# abletondevicecontroller.net
KiCad netlist of a schematic drawn in EAGLE
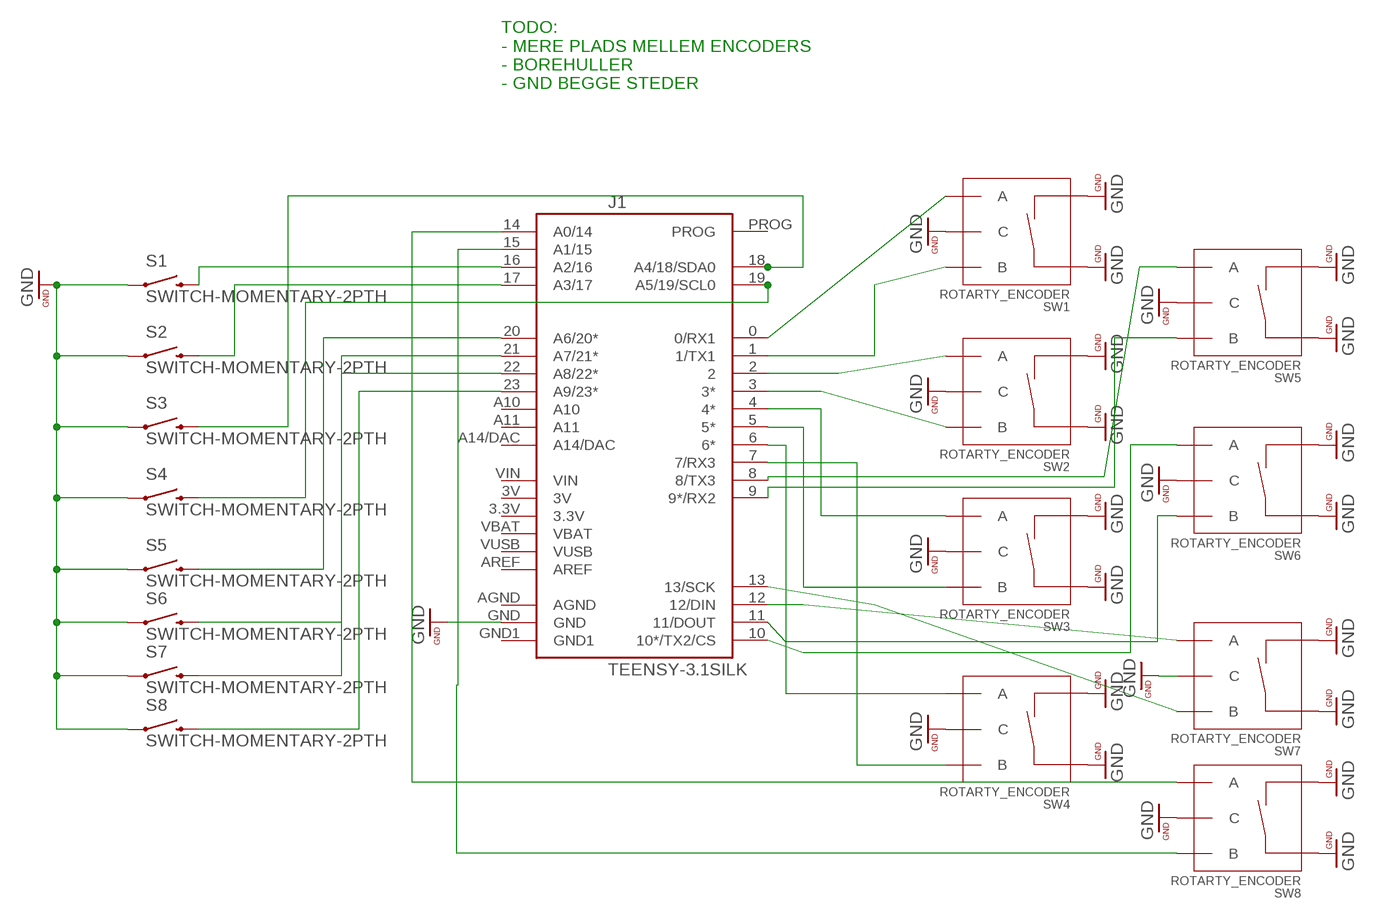
[diagram p0: schematic, sheet 1]

(export (version "E")
  (design (tool "Eeschema 10.0.6"))
  (components
    (comp (ref "J1")
      (value "TEENSY-3.1SILK")
      (footprint "eagle-import:TEENSY-3.1")
      (libsource (lib "eagle-import") (part "TEENSY-3.1SILK"))
    )
    (comp (ref "S1")
      (value "SWITCH-MOMENTARY-2PTH")
      (footprint "eagle-import:TACTILE-PTH")
      (libsource (lib "eagle-import") (part "SWITCH-MOMENTARY-2PTH"))
    )
    (comp (ref "S2")
      (value "SWITCH-MOMENTARY-2PTH")
      (footprint "eagle-import:TACTILE-PTH")
      (libsource (lib "eagle-import") (part "SWITCH-MOMENTARY-2PTH"))
    )
    (comp (ref "S3")
      (value "SWITCH-MOMENTARY-2PTH")
      (footprint "eagle-import:TACTILE-PTH")
      (libsource (lib "eagle-import") (part "SWITCH-MOMENTARY-2PTH"))
    )
    (comp (ref "S4")
      (value "SWITCH-MOMENTARY-2PTH")
      (footprint "eagle-import:TACTILE-PTH")
      (libsource (lib "eagle-import") (part "SWITCH-MOMENTARY-2PTH"))
    )
    (comp (ref "S5")
      (value "SWITCH-MOMENTARY-2PTH")
      (footprint "eagle-import:TACTILE-PTH")
      (libsource (lib "eagle-import") (part "SWITCH-MOMENTARY-2PTH"))
    )
    (comp (ref "S6")
      (value "SWITCH-MOMENTARY-2PTH")
      (footprint "eagle-import:TACTILE-PTH")
      (libsource (lib "eagle-import") (part "SWITCH-MOMENTARY-2PTH"))
    )
    (comp (ref "S7")
      (value "SWITCH-MOMENTARY-2PTH")
      (footprint "eagle-import:TACTILE-PTH")
      (libsource (lib "eagle-import") (part "SWITCH-MOMENTARY-2PTH"))
    )
    (comp (ref "S8")
      (value "SWITCH-MOMENTARY-2PTH")
      (footprint "eagle-import:TACTILE-PTH")
      (libsource (lib "eagle-import") (part "SWITCH-MOMENTARY-2PTH"))
    )
    (comp (ref "SW1")
      (value "ROTARTY_ENCODER")
      (footprint "eagle-import:ROTARY_ENC_PLAIN")
      (libsource (lib "eagle-import") (part "ROTARTY_ENCODER"))
    )
    (comp (ref "SW2")
      (value "ROTARTY_ENCODER")
      (footprint "eagle-import:ROTARY_ENC_PLAIN")
      (libsource (lib "eagle-import") (part "ROTARTY_ENCODER"))
    )
    (comp (ref "SW3")
      (value "ROTARTY_ENCODER")
      (footprint "eagle-import:ROTARY_ENC_PLAIN")
      (libsource (lib "eagle-import") (part "ROTARTY_ENCODER"))
    )
    (comp (ref "SW4")
      (value "ROTARTY_ENCODER")
      (footprint "eagle-import:ROTARY_ENC_PLAIN")
      (libsource (lib "eagle-import") (part "ROTARTY_ENCODER"))
    )
    (comp (ref "SW5")
      (value "ROTARTY_ENCODER")
      (footprint "eagle-import:ROTARY_ENC_PLAIN")
      (libsource (lib "eagle-import") (part "ROTARTY_ENCODER"))
    )
    (comp (ref "SW6")
      (value "ROTARTY_ENCODER")
      (footprint "eagle-import:ROTARY_ENC_PLAIN")
      (libsource (lib "eagle-import") (part "ROTARTY_ENCODER"))
    )
    (comp (ref "SW7")
      (value "ROTARTY_ENCODER")
      (footprint "eagle-import:ROTARY_ENC_PLAIN")
      (libsource (lib "eagle-import") (part "ROTARTY_ENCODER"))
    )
    (comp (ref "SW8")
      (value "ROTARTY_ENCODER")
      (footprint "eagle-import:ROTARY_ENC_PLAIN")
      (libsource (lib "eagle-import") (part "ROTARTY_ENCODER"))
    )
  )
  (nets
    (net (code "1") (name "GND") (class "Default")
      (node (ref "J1") (pin "GND") (pinfunction "GND_GND") (pintype "bidirectional"))
      (node (ref "S1") (pin "1") (pinfunction "1_1") (pintype "passive"))
      (node (ref "S2") (pin "1") (pinfunction "1_1") (pintype "passive"))
      (node (ref "S3") (pin "1") (pinfunction "1_1") (pintype "passive"))
      (node (ref "S4") (pin "1") (pinfunction "1_1") (pintype "passive"))
      (node (ref "S5") (pin "1") (pinfunction "1_1") (pintype "passive"))
      (node (ref "S6") (pin "1") (pinfunction "1_1") (pintype "passive"))
      (node (ref "S7") (pin "1") (pinfunction "1_1") (pintype "passive"))
      (node (ref "S8") (pin "1") (pinfunction "1_1") (pintype "passive"))
      (node (ref "SW1") (pin "C") (pinfunction "C_C") (pintype "bidirectional"))
      (node (ref "SW1") (pin "SW+") (pinfunction "SW+_SW+") (pintype "bidirectional"))
      (node (ref "SW1") (pin "SW-") (pinfunction "SW-_SW-") (pintype "bidirectional"))
      (node (ref "SW2") (pin "C") (pinfunction "C_C") (pintype "bidirectional"))
      (node (ref "SW2") (pin "SW+") (pinfunction "SW+_SW+") (pintype "bidirectional"))
      (node (ref "SW2") (pin "SW-") (pinfunction "SW-_SW-") (pintype "bidirectional"))
      (node (ref "SW3") (pin "C") (pinfunction "C_C") (pintype "bidirectional"))
      (node (ref "SW3") (pin "SW+") (pinfunction "SW+_SW+") (pintype "bidirectional"))
      (node (ref "SW3") (pin "SW-") (pinfunction "SW-_SW-") (pintype "bidirectional"))
      (node (ref "SW4") (pin "C") (pinfunction "C_C") (pintype "bidirectional"))
      (node (ref "SW4") (pin "SW+") (pinfunction "SW+_SW+") (pintype "bidirectional"))
      (node (ref "SW4") (pin "SW-") (pinfunction "SW-_SW-") (pintype "bidirectional"))
      (node (ref "SW5") (pin "C") (pinfunction "C_C") (pintype "bidirectional"))
      (node (ref "SW5") (pin "SW+") (pinfunction "SW+_SW+") (pintype "bidirectional"))
      (node (ref "SW5") (pin "SW-") (pinfunction "SW-_SW-") (pintype "bidirectional"))
      (node (ref "SW6") (pin "C") (pinfunction "C_C") (pintype "bidirectional"))
      (node (ref "SW6") (pin "SW+") (pinfunction "SW+_SW+") (pintype "bidirectional"))
      (node (ref "SW6") (pin "SW-") (pinfunction "SW-_SW-") (pintype "bidirectional"))
      (node (ref "SW7") (pin "C") (pinfunction "C_C") (pintype "bidirectional"))
      (node (ref "SW7") (pin "SW+") (pinfunction "SW+_SW+") (pintype "bidirectional"))
      (node (ref "SW7") (pin "SW-") (pinfunction "SW-_SW-") (pintype "bidirectional"))
      (node (ref "SW8") (pin "C") (pinfunction "C_C") (pintype "bidirectional"))
      (node (ref "SW8") (pin "SW+") (pinfunction "SW+_SW+") (pintype "bidirectional"))
      (node (ref "SW8") (pin "SW-") (pinfunction "SW-_SW-") (pintype "bidirectional"))
    )
    (net (code "2") (name "Net-(J1-0{slash}RX1)") (class "Default")
      (node (ref "J1") (pin "0") (pinfunction "0/RX1_0") (pintype "bidirectional"))
      (node (ref "SW1") (pin "A") (pinfunction "A_A") (pintype "bidirectional"))
    )
    (net (code "3") (name "Net-(J1-1{slash}TX1)") (class "Default")
      (node (ref "J1") (pin "1") (pinfunction "1/TX1_1") (pintype "bidirectional"))
      (node (ref "SW1") (pin "B") (pinfunction "B_B") (pintype "bidirectional"))
    )
    (net (code "4") (name "Net-(J1-3*)") (class "Default")
      (node (ref "J1") (pin "3") (pinfunction "3*_3") (pintype "bidirectional"))
      (node (ref "SW2") (pin "B") (pinfunction "B_B") (pintype "bidirectional"))
    )
    (net (code "5") (name "Net-(J1-4*)") (class "Default")
      (node (ref "J1") (pin "4") (pinfunction "4*_4") (pintype "bidirectional"))
      (node (ref "SW3") (pin "A") (pinfunction "A_A") (pintype "bidirectional"))
    )
    (net (code "6") (name "Net-(J1-5*)") (class "Default")
      (node (ref "J1") (pin "5") (pinfunction "5*_5") (pintype "bidirectional"))
      (node (ref "SW3") (pin "B") (pinfunction "B_B") (pintype "bidirectional"))
    )
    (net (code "7") (name "Net-(J1-6*)") (class "Default")
      (node (ref "J1") (pin "6") (pinfunction "6*_6") (pintype "bidirectional"))
      (node (ref "SW4") (pin "A") (pinfunction "A_A") (pintype "bidirectional"))
    )
    (net (code "8") (name "Net-(J1-7{slash}RX3)") (class "Default")
      (node (ref "J1") (pin "7") (pinfunction "7/RX3_7") (pintype "bidirectional"))
      (node (ref "SW4") (pin "B") (pinfunction "B_B") (pintype "bidirectional"))
    )
    (net (code "9") (name "Net-(J1-8{slash}TX3)") (class "Default")
      (node (ref "J1") (pin "8") (pinfunction "8/TX3_8") (pintype "bidirectional"))
      (node (ref "SW5") (pin "A") (pinfunction "A_A") (pintype "bidirectional"))
    )
    (net (code "10") (name "Net-(J1-9*{slash}RX2)") (class "Default")
      (node (ref "J1") (pin "9") (pinfunction "9*/RX2_9") (pintype "bidirectional"))
      (node (ref "SW5") (pin "B") (pinfunction "B_B") (pintype "bidirectional"))
    )
    (net (code "11") (name "Net-(J1-10*{slash}TX2{slash}CS)") (class "Default")
      (node (ref "J1") (pin "10") (pinfunction "10*/TX2/CS_10") (pintype "bidirectional"))
      (node (ref "SW6") (pin "A") (pinfunction "A_A") (pintype "bidirectional"))
    )
    (net (code "12") (name "Net-(J1-11{slash}DOUT)") (class "Default")
      (node (ref "J1") (pin "11") (pinfunction "11/DOUT_11") (pintype "bidirectional"))
      (node (ref "SW6") (pin "B") (pinfunction "B_B") (pintype "bidirectional"))
    )
    (net (code "13") (name "Net-(J1-12{slash}DIN)") (class "Default")
      (node (ref "J1") (pin "12") (pinfunction "12/DIN_12") (pintype "bidirectional"))
      (node (ref "SW7") (pin "A") (pinfunction "A_A") (pintype "bidirectional"))
    )
    (net (code "14") (name "Net-(J1-13{slash}SCK)") (class "Default")
      (node (ref "J1") (pin "13") (pinfunction "13/SCK_13") (pintype "bidirectional"))
      (node (ref "SW7") (pin "B") (pinfunction "B_B") (pintype "bidirectional"))
    )
    (net (code "15") (name "Net-(J1-A0{slash}14)") (class "Default")
      (node (ref "J1") (pin "14") (pinfunction "A0/14_14") (pintype "bidirectional"))
      (node (ref "SW8") (pin "A") (pinfunction "A_A") (pintype "bidirectional"))
    )
    (net (code "16") (name "Net-(J1-A1{slash}15)") (class "Default")
      (node (ref "J1") (pin "15") (pinfunction "A1/15_15") (pintype "bidirectional"))
      (node (ref "SW8") (pin "B") (pinfunction "B_B") (pintype "bidirectional"))
    )
    (net (code "17") (name "Net-(J1-A2{slash}16)") (class "Default")
      (node (ref "J1") (pin "16") (pinfunction "A2/16_16") (pintype "bidirectional"))
      (node (ref "S1") (pin "3") (pinfunction "2_3") (pintype "passive"))
    )
    (net (code "18") (name "Net-(J1-A3{slash}17)") (class "Default")
      (node (ref "J1") (pin "17") (pinfunction "A3/17_17") (pintype "bidirectional"))
      (node (ref "S2") (pin "3") (pinfunction "2_3") (pintype "passive"))
    )
    (net (code "19") (name "Net-(J1-A4{slash}18{slash}SDA0)") (class "Default")
      (node (ref "J1") (pin "18") (pinfunction "A4/18/SDA0_18") (pintype "bidirectional"))
      (node (ref "S3") (pin "3") (pinfunction "2_3") (pintype "passive"))
    )
    (net (code "20") (name "Net-(J1-A5{slash}19{slash}SCL0)") (class "Default")
      (node (ref "J1") (pin "19") (pinfunction "A5/19/SCL0_19") (pintype "bidirectional"))
      (node (ref "S4") (pin "3") (pinfunction "2_3") (pintype "passive"))
    )
    (net (code "21") (name "Net-(J1-A6{slash}20*)") (class "Default")
      (node (ref "J1") (pin "20") (pinfunction "A6/20*_20") (pintype "bidirectional"))
      (node (ref "S5") (pin "3") (pinfunction "2_3") (pintype "passive"))
    )
    (net (code "22") (name "Net-(J1-A7{slash}21*)") (class "Default")
      (node (ref "J1") (pin "21") (pinfunction "A7/21*_21") (pintype "bidirectional"))
      (node (ref "S6") (pin "3") (pinfunction "2_3") (pintype "passive"))
    )
    (net (code "23") (name "Net-(J1-A8{slash}22*)") (class "Default")
      (node (ref "J1") (pin "22") (pinfunction "A8/22*_22") (pintype "bidirectional"))
      (node (ref "S7") (pin "3") (pinfunction "2_3") (pintype "passive"))
    )
    (net (code "24") (name "Net-(J1-A9{slash}23*)") (class "Default")
      (node (ref "J1") (pin "23") (pinfunction "A9/23*_23") (pintype "bidirectional"))
      (node (ref "S8") (pin "3") (pinfunction "2_3") (pintype "passive"))
    )
    (net (code "25") (name "Net-(J1-Pad2)") (class "Default")
      (node (ref "J1") (pin "2") (pinfunction "2_2") (pintype "bidirectional"))
      (node (ref "SW2") (pin "A") (pinfunction "A_A") (pintype "bidirectional"))
    )
    (net (code "26") (name "unconnected-(J1-Pad3.3V)") (class "Default")
      (node (ref "J1") (pin "3.3V") (pinfunction "3.3V_3.3V") (pintype "bidirectional"))
    )
    (net (code "27") (name "unconnected-(J1-Pad3V)") (class "Default")
      (node (ref "J1") (pin "3V") (pinfunction "3V_3V") (pintype "bidirectional"))
    )
    (net (code "28") (name "unconnected-(J1-PadA10)") (class "Default")
      (node (ref "J1") (pin "A10") (pinfunction "A10_A10") (pintype "bidirectional"))
    )
    (net (code "29") (name "unconnected-(J1-PadA11)") (class "Default")
      (node (ref "J1") (pin "A11") (pinfunction "A11_A11") (pintype "bidirectional"))
    )
    (net (code "30") (name "unconnected-(J1-PadA14{slash}DAC)") (class "Default")
      (node (ref "J1") (pin "A14/DAC") (pinfunction "A14/DAC_A14/DAC") (pintype "bidirectional"))
    )
    (net (code "31") (name "unconnected-(J1-PadAGND)") (class "Default")
      (node (ref "J1") (pin "AGND") (pinfunction "AGND_AGND") (pintype "bidirectional"))
    )
    (net (code "32") (name "unconnected-(J1-PadAREF)") (class "Default")
      (node (ref "J1") (pin "AREF") (pinfunction "AREF_AREF") (pintype "bidirectional"))
    )
    (net (code "33") (name "unconnected-(J1-PadGND1)") (class "Default")
      (node (ref "J1") (pin "GND1") (pinfunction "GND1_GND1") (pintype "bidirectional"))
    )
    (net (code "34") (name "unconnected-(J1-PadPROG)") (class "Default")
      (node (ref "J1") (pin "PROG") (pinfunction "PROG_PROG") (pintype "bidirectional"))
    )
    (net (code "35") (name "unconnected-(J1-PadVBAT)") (class "Default")
      (node (ref "J1") (pin "VBAT") (pinfunction "VBAT_VBAT") (pintype "bidirectional"))
    )
    (net (code "36") (name "unconnected-(J1-PadVIN)") (class "Default")
      (node (ref "J1") (pin "VIN") (pinfunction "VIN_VIN") (pintype "bidirectional"))
    )
    (net (code "37") (name "unconnected-(J1-PadVUSB)") (class "Default")
      (node (ref "J1") (pin "VUSB") (pinfunction "VUSB_VUSB") (pintype "bidirectional"))
    )
  )
)
